# joulethief.net
KiCad netlist of a schematic drawn in EAGLE
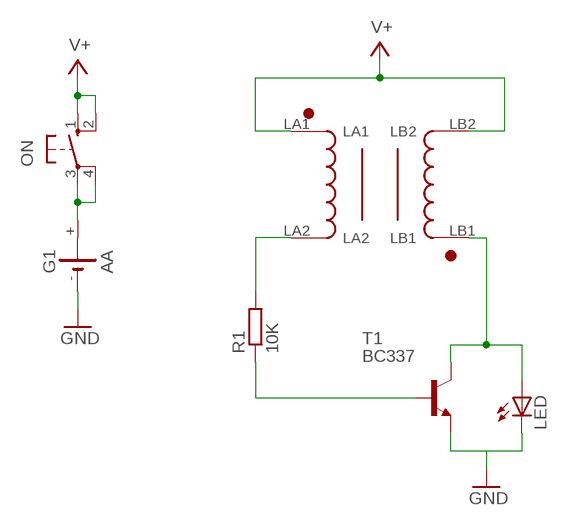
[diagram p0: schematic, sheet 1]

(export (version "E")
  (design (tool "Eeschema 10.0.6"))
  (components
    (comp (ref "G1")
      (value "AA")
      (footprint "eagle-import:AA-HOLDER")
      (libsource (lib "eagle-import") (part "AA"))
    )
    (comp (ref "LED")
      (value "LED5MM")
      (footprint "eagle-import:LED5MM")
      (libsource (lib "eagle-import") (part "LED5MM"))
    )
    (comp (ref "ON")
      (value "10-XX")
      (footprint "eagle-import:B3F-10XX")
      (fields (field (name "MPN") "B3F-1000"))
      (libsource (lib "eagle-import") (part "10-XX"))
    )
    (comp (ref "R1")
      (value "10K")
      (footprint "eagle-import:0207_10")
      (libsource (lib "eagle-import") (part "R-EU_0207/10"))
    )
    (comp (ref "T1")
      (value "BC337")
      (footprint "eagle-import:TO92")
      (libsource (lib "eagle-import") (part "BC337"))
    )
    (comp (ref "U$1")
      (value "COIL-BEAD")
      (footprint "eagle-import:BEAD-22-13.8-6.4")
      (libsource (lib "eagle-import") (part "COIL-BEAD"))
    )
  )
  (nets
    (net (code "1") (name "GND") (class "Default")
      (node (ref "G1") (pin "-") (pinfunction "-_-") (pintype "passive"))
      (node (ref "LED") (pin "K") (pinfunction "C_K") (pintype "passive"))
      (node (ref "T1") (pin "1") (pinfunction "E_1") (pintype "passive"))
    )
    (net (code "2") (name "Net-(ON-P)") (class "Default")
      (node (ref "G1") (pin "+") (pinfunction "+_+") (pintype "passive"))
      (node (ref "ON") (pin "3") (pinfunction "P_3") (pintype "passive"))
      (node (ref "ON") (pin "4") (pinfunction "P1_4") (pintype "passive"))
    )
    (net (code "3") (name "Net-(R1-Pad2)") (class "Default")
      (node (ref "R1") (pin "2") (pinfunction "2_2") (pintype "passive"))
      (node (ref "U$1") (pin "LA2") (pinfunction "LA2_LA2") (pintype "bidirectional"))
    )
    (net (code "4") (name "Net-(T1-B)") (class "Default")
      (node (ref "R1") (pin "1") (pinfunction "1_1") (pintype "passive"))
      (node (ref "T1") (pin "2") (pinfunction "B_2") (pintype "passive"))
    )
    (net (code "5") (name "Net-(T1-C)") (class "Default")
      (node (ref "LED") (pin "A") (pinfunction "A_A") (pintype "passive"))
      (node (ref "T1") (pin "3") (pinfunction "C_3") (pintype "passive"))
      (node (ref "U$1") (pin "LB1") (pinfunction "LB1_LB1") (pintype "bidirectional"))
    )
    (net (code "6") (name "V+") (class "Default")
      (node (ref "ON") (pin "1") (pinfunction "S_1") (pintype "passive"))
      (node (ref "ON") (pin "2") (pinfunction "S1_2") (pintype "passive"))
      (node (ref "U$1") (pin "LA1") (pinfunction "LA1_LA1") (pintype "bidirectional"))
      (node (ref "U$1") (pin "LB2") (pinfunction "LB2_LB2") (pintype "bidirectional"))
    )
  )
)
